# DualBalancedOutput.net
KiCad netlist of a schematic drawn in EAGLE
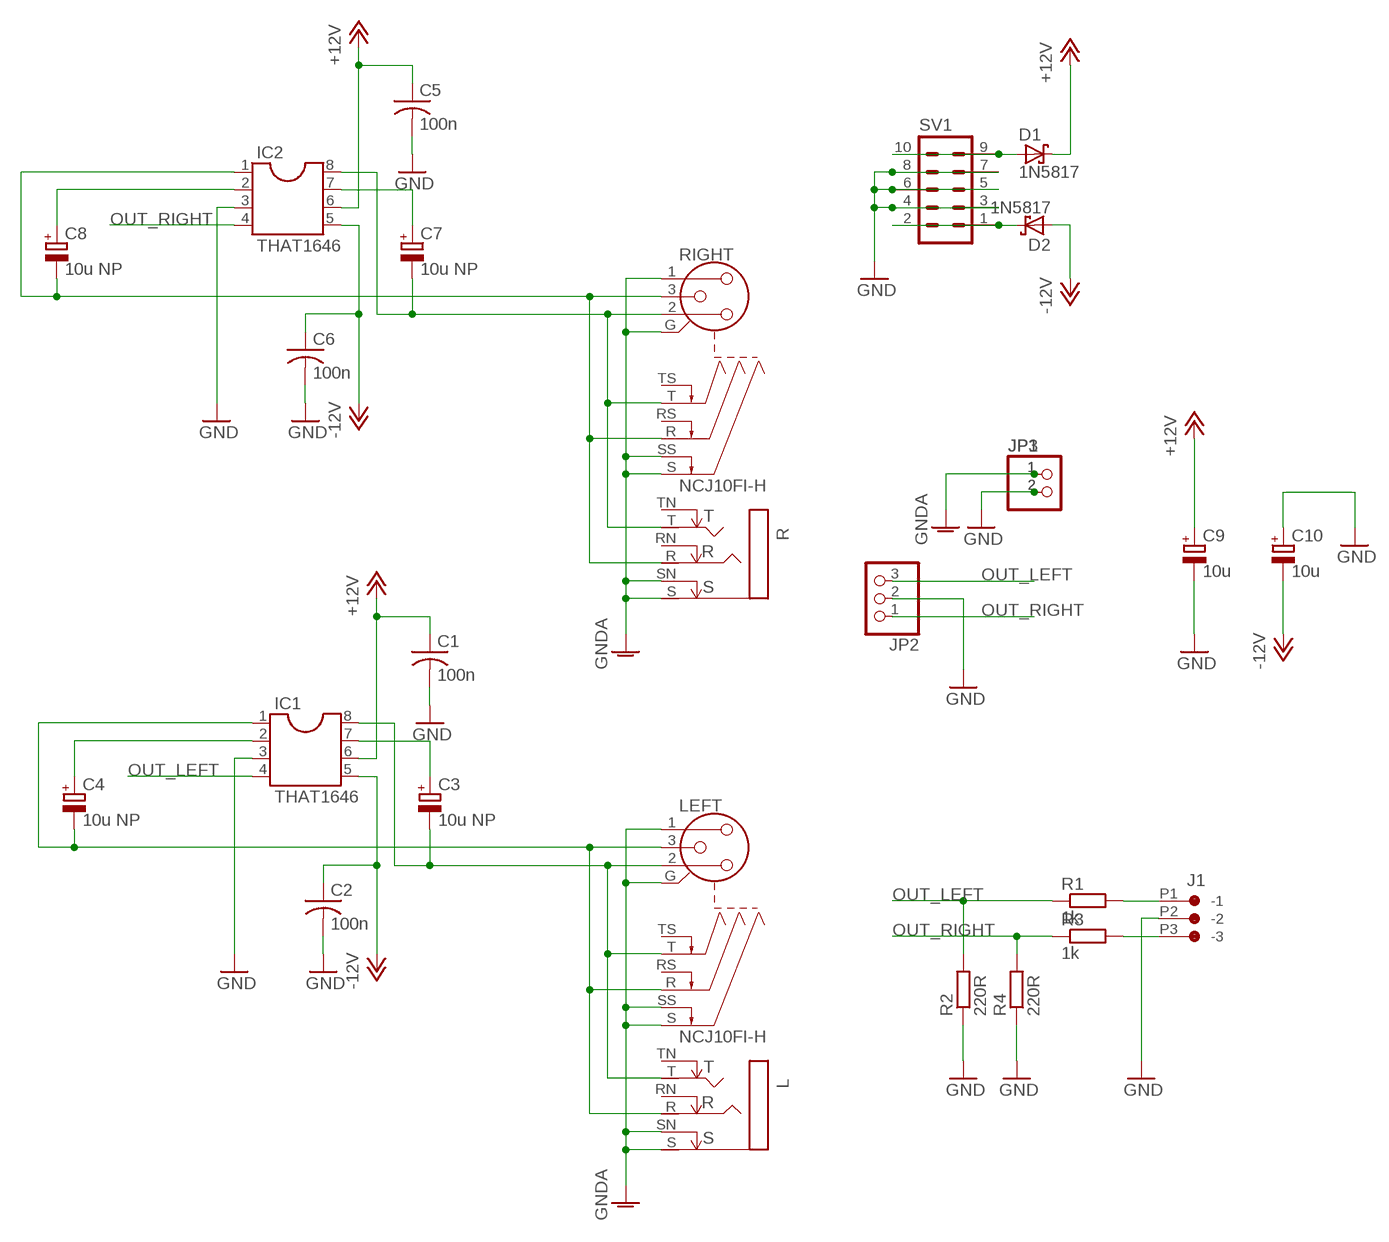
[diagram p0: schematic, sheet 1]

(export (version "E")
  (design (tool "Eeschema 10.0.6"))
  (components
    (comp (ref "C1")
      (value "100n")
      (footprint "eagle-import:C050-024X044")
      (libsource (lib "eagle-import") (part "C-US050-024X044"))
    )
    (comp (ref "C2")
      (value "100n")
      (footprint "eagle-import:C050-024X044")
      (libsource (lib "eagle-import") (part "C-US050-024X044"))
    )
    (comp (ref "C3")
      (value "10u NP")
      (footprint "eagle-import:E2-5")
      (libsource (lib "eagle-import") (part "CPOL-EUE2-5"))
    )
    (comp (ref "C4")
      (value "10u NP")
      (footprint "eagle-import:E2-5")
      (libsource (lib "eagle-import") (part "CPOL-EUE2-5"))
    )
    (comp (ref "C5")
      (value "100n")
      (footprint "eagle-import:C050-024X044")
      (libsource (lib "eagle-import") (part "C-US050-024X044"))
    )
    (comp (ref "C6")
      (value "100n")
      (footprint "eagle-import:C050-024X044")
      (libsource (lib "eagle-import") (part "C-US050-024X044"))
    )
    (comp (ref "C7")
      (value "10u NP")
      (footprint "eagle-import:E2-5")
      (libsource (lib "eagle-import") (part "CPOL-EUE2-5"))
    )
    (comp (ref "C8")
      (value "10u NP")
      (footprint "eagle-import:E2-5")
      (libsource (lib "eagle-import") (part "CPOL-EUE2-5"))
    )
    (comp (ref "C9")
      (value "10u")
      (footprint "eagle-import:E5-6")
      (libsource (lib "eagle-import") (part "rcl_CPOL-EUE5-6"))
    )
    (comp (ref "C10")
      (value "10u")
      (footprint "eagle-import:E5-6")
      (libsource (lib "eagle-import") (part "rcl_CPOL-EUE5-6"))
    )
    (comp (ref "D1")
      (value "1N5817")
      (footprint "eagle-import:DO41-7.6")
      (libsource (lib "eagle-import") (part "1N5819-B"))
    )
    (comp (ref "D2")
      (value "1N5817")
      (footprint "eagle-import:DO41-7.6")
      (libsource (lib "eagle-import") (part "1N5819-B"))
    )
    (comp (ref "IC1")
      (value "THAT1646")
      (footprint "eagle-import:DIL08")
      (libsource (lib "eagle-import") (part "DIL8"))
    )
    (comp (ref "IC2")
      (value "THAT1646")
      (footprint "eagle-import:DIL08")
      (libsource (lib "eagle-import") (part "DIL8"))
    )
    (comp (ref "J1")
      (value "CON-JST_PH_3W")
      (footprint "eagle-import:CON-JST_PH_3W")
      (libsource (lib "eagle-import") (part "CON-JST_PH_3W"))
    )
    (comp (ref "JP1")
      (value "PINHD-1X2")
      (footprint "eagle-import:1X02")
      (libsource (lib "eagle-import") (part "PINHD-1X2"))
    )
    (comp (ref "JP2")
      (value "PINHD-1X3")
      (footprint "eagle-import:1X03")
      (libsource (lib "eagle-import") (part "PINHD-1X3"))
    )
    (comp (ref "JP3")
      (value "PINHD-1X2")
      (footprint "eagle-import:1X02")
      (libsource (lib "eagle-import") (part "PINHD-1X2"))
    )
    (comp (ref "L")
      (value "NEUTRIK_NMJ6HCD2")
      (footprint "eagle-import:NMJ6HCD2")
      (libsource (lib "eagle-import") (part "NEUTRIK_NMJ6HCD2"))
    )
    (comp (ref "LEFT")
      (value "NCJ10FI-H")
      (footprint "eagle-import:NCJ10FI-H")
      (libsource (lib "eagle-import") (part "NCJ10FI-H"))
    )
    (comp (ref "R")
      (value "NEUTRIK_NMJ6HCD2")
      (footprint "eagle-import:NMJ6HCD2")
      (libsource (lib "eagle-import") (part "NEUTRIK_NMJ6HCD2"))
    )
    (comp (ref "R1")
      (value "1k")
      (footprint "eagle-import:0204_7")
      (libsource (lib "eagle-import") (part "R-EU_0204/7"))
    )
    (comp (ref "R2")
      (value "220R")
      (footprint "eagle-import:0204_7")
      (libsource (lib "eagle-import") (part "R-EU_0204/7"))
    )
    (comp (ref "R3")
      (value "1k")
      (footprint "eagle-import:0204_7")
      (libsource (lib "eagle-import") (part "R-EU_0204/7"))
    )
    (comp (ref "R4")
      (value "220R")
      (footprint "eagle-import:0204_7")
      (libsource (lib "eagle-import") (part "R-EU_0204/7"))
    )
    (comp (ref "RIGHT")
      (value "NCJ10FI-H")
      (footprint "eagle-import:NCJ10FI-H")
      (libsource (lib "eagle-import") (part "NCJ10FI-H"))
    )
    (comp (ref "SV1")
      (value "MA05-2")
      (footprint "eagle-import:MA05-2")
      (libsource (lib "eagle-import") (part "MA05-2"))
    )
  )
  (nets
    (net (code "1") (name "+12V") (class "Default")
      (node (ref "C1") (pin "1") (pinfunction "1_1") (pintype "passive"))
      (node (ref "C5") (pin "1") (pinfunction "1_1") (pintype "passive"))
      (node (ref "C9") (pin "+") (pinfunction "+_+") (pintype "passive"))
      (node (ref "D1") (pin "C") (pinfunction "C_C") (pintype "passive"))
      (node (ref "IC1") (pin "6") (pinfunction "6_6") (pintype "passive"))
      (node (ref "IC2") (pin "6") (pinfunction "6_6") (pintype "passive"))
    )
    (net (code "2") (name "-12V") (class "Default")
      (node (ref "C10") (pin "-") (pinfunction "-_-") (pintype "passive"))
      (node (ref "C2") (pin "1") (pinfunction "1_1") (pintype "passive"))
      (node (ref "C6") (pin "1") (pinfunction "1_1") (pintype "passive"))
      (node (ref "D2") (pin "A") (pinfunction "A_A") (pintype "passive"))
      (node (ref "IC1") (pin "5") (pinfunction "5_5") (pintype "passive"))
      (node (ref "IC2") (pin "5") (pinfunction "5_5") (pintype "passive"))
    )
    (net (code "3") (name "/OUT_LEFT") (class "Default")
      (node (ref "IC1") (pin "4") (pinfunction "4_4") (pintype "passive"))
      (node (ref "JP2") (pin "3") (pinfunction "3_3") (pintype "passive"))
      (node (ref "R1") (pin "1") (pinfunction "1_1") (pintype "passive"))
      (node (ref "R2") (pin "2") (pinfunction "2_2") (pintype "passive"))
    )
    (net (code "4") (name "/OUT_RIGHT") (class "Default")
      (node (ref "IC2") (pin "4") (pinfunction "4_4") (pintype "passive"))
      (node (ref "JP2") (pin "1") (pinfunction "1_1") (pintype "passive"))
      (node (ref "R3") (pin "1") (pinfunction "1_1") (pintype "passive"))
      (node (ref "R4") (pin "2") (pinfunction "2_2") (pintype "passive"))
    )
    (net (code "5") (name "GND") (class "Default")
      (node (ref "C1") (pin "2") (pinfunction "2_2") (pintype "passive"))
      (node (ref "C10") (pin "+") (pinfunction "+_+") (pintype "passive"))
      (node (ref "C2") (pin "2") (pinfunction "2_2") (pintype "passive"))
      (node (ref "C5") (pin "2") (pinfunction "2_2") (pintype "passive"))
      (node (ref "C6") (pin "2") (pinfunction "2_2") (pintype "passive"))
      (node (ref "C9") (pin "-") (pinfunction "-_-") (pintype "passive"))
      (node (ref "IC1") (pin "3") (pinfunction "3_3") (pintype "passive"))
      (node (ref "IC2") (pin "3") (pinfunction "3_3") (pintype "passive"))
      (node (ref "J1") (pin "P2") (pinfunction "-2_P2") (pintype "bidirectional"))
      (node (ref "JP1") (pin "2") (pinfunction "2_2") (pintype "passive"))
      (node (ref "JP2") (pin "2") (pinfunction "2_2") (pintype "passive"))
      (node (ref "JP3") (pin "2") (pinfunction "2_2") (pintype "passive"))
      (node (ref "R2") (pin "1") (pinfunction "1_1") (pintype "passive"))
      (node (ref "R4") (pin "1") (pinfunction "1_1") (pintype "passive"))
      (node (ref "SV1") (pin "3") (pinfunction "3_3") (pintype "passive"))
      (node (ref "SV1") (pin "4") (pinfunction "4_4") (pintype "passive"))
      (node (ref "SV1") (pin "5") (pinfunction "5_5") (pintype "passive"))
      (node (ref "SV1") (pin "6") (pinfunction "6_6") (pintype "passive"))
      (node (ref "SV1") (pin "7") (pinfunction "7_7") (pintype "passive"))
      (node (ref "SV1") (pin "8") (pinfunction "8_8") (pintype "passive"))
    )
    (net (code "6") (name "GNDA") (class "Default")
      (node (ref "JP1") (pin "1") (pinfunction "1_1") (pintype "passive"))
      (node (ref "JP3") (pin "1") (pinfunction "1_1") (pintype "passive"))
      (node (ref "L") (pin "S") (pinfunction "S_S") (pintype "passive"))
      (node (ref "L") (pin "SN") (pinfunction "SN_SN") (pintype "passive"))
      (node (ref "LEFT") (pin "1") (pinfunction "1_1") (pintype "passive"))
      (node (ref "LEFT") (pin "G") (pinfunction "G_G") (pintype "passive"))
      (node (ref "LEFT") (pin "S") (pinfunction "S_S") (pintype "passive"))
      (node (ref "LEFT") (pin "SS") (pinfunction "SS_SS") (pintype "passive"))
      (node (ref "R") (pin "S") (pinfunction "S_S") (pintype "passive"))
      (node (ref "R") (pin "SN") (pinfunction "SN_SN") (pintype "passive"))
      (node (ref "RIGHT") (pin "1") (pinfunction "1_1") (pintype "passive"))
      (node (ref "RIGHT") (pin "G") (pinfunction "G_G") (pintype "passive"))
      (node (ref "RIGHT") (pin "S") (pinfunction "S_S") (pintype "passive"))
      (node (ref "RIGHT") (pin "SS") (pinfunction "SS_SS") (pintype "passive"))
    )
    (net (code "7") (name "Net-(C3-Pad+)") (class "Default")
      (node (ref "C3") (pin "+") (pinfunction "+_+") (pintype "passive"))
      (node (ref "IC1") (pin "7") (pinfunction "7_7") (pintype "passive"))
    )
    (net (code "8") (name "Net-(C3-Pad-)") (class "Default")
      (node (ref "C3") (pin "-") (pinfunction "-_-") (pintype "passive"))
      (node (ref "IC1") (pin "8") (pinfunction "8_8") (pintype "passive"))
      (node (ref "L") (pin "T") (pinfunction "T_T") (pintype "passive"))
      (node (ref "LEFT") (pin "2") (pinfunction "2_2") (pintype "passive"))
      (node (ref "LEFT") (pin "T") (pinfunction "T_T") (pintype "passive"))
    )
    (net (code "9") (name "Net-(C4-Pad+)") (class "Default")
      (node (ref "C4") (pin "+") (pinfunction "+_+") (pintype "passive"))
      (node (ref "IC1") (pin "2") (pinfunction "2_2") (pintype "passive"))
    )
    (net (code "10") (name "Net-(C4-Pad-)") (class "Default")
      (node (ref "C4") (pin "-") (pinfunction "-_-") (pintype "passive"))
      (node (ref "IC1") (pin "1") (pinfunction "1_1") (pintype "passive"))
      (node (ref "L") (pin "R") (pinfunction "R_R") (pintype "passive"))
      (node (ref "LEFT") (pin "3") (pinfunction "3_3") (pintype "passive"))
      (node (ref "LEFT") (pin "R") (pinfunction "R_R") (pintype "passive"))
    )
    (net (code "11") (name "Net-(C7-Pad+)") (class "Default")
      (node (ref "C7") (pin "+") (pinfunction "+_+") (pintype "passive"))
      (node (ref "IC2") (pin "7") (pinfunction "7_7") (pintype "passive"))
    )
    (net (code "12") (name "Net-(C7-Pad-)") (class "Default")
      (node (ref "C7") (pin "-") (pinfunction "-_-") (pintype "passive"))
      (node (ref "IC2") (pin "8") (pinfunction "8_8") (pintype "passive"))
      (node (ref "R") (pin "T") (pinfunction "T_T") (pintype "passive"))
      (node (ref "RIGHT") (pin "2") (pinfunction "2_2") (pintype "passive"))
      (node (ref "RIGHT") (pin "T") (pinfunction "T_T") (pintype "passive"))
    )
    (net (code "13") (name "Net-(C8-Pad+)") (class "Default")
      (node (ref "C8") (pin "+") (pinfunction "+_+") (pintype "passive"))
      (node (ref "IC2") (pin "2") (pinfunction "2_2") (pintype "passive"))
    )
    (net (code "14") (name "Net-(C8-Pad-)") (class "Default")
      (node (ref "C8") (pin "-") (pinfunction "-_-") (pintype "passive"))
      (node (ref "IC2") (pin "1") (pinfunction "1_1") (pintype "passive"))
      (node (ref "R") (pin "R") (pinfunction "R_R") (pintype "passive"))
      (node (ref "RIGHT") (pin "3") (pinfunction "3_3") (pintype "passive"))
      (node (ref "RIGHT") (pin "R") (pinfunction "R_R") (pintype "passive"))
    )
    (net (code "15") (name "Net-(D1-PadA)") (class "Default")
      (node (ref "D1") (pin "A") (pinfunction "A_A") (pintype "passive"))
      (node (ref "SV1") (pin "10") (pinfunction "10_10") (pintype "passive"))
      (node (ref "SV1") (pin "9") (pinfunction "9_9") (pintype "passive"))
    )
    (net (code "16") (name "Net-(D2-PadC)") (class "Default")
      (node (ref "D2") (pin "C") (pinfunction "C_C") (pintype "passive"))
      (node (ref "SV1") (pin "1") (pinfunction "1_1") (pintype "passive"))
      (node (ref "SV1") (pin "2") (pinfunction "2_2") (pintype "passive"))
    )
    (net (code "17") (name "Net-(J1--1)") (class "Default")
      (node (ref "J1") (pin "P1") (pinfunction "-1_P1") (pintype "bidirectional"))
      (node (ref "R1") (pin "2") (pinfunction "2_2") (pintype "passive"))
    )
    (net (code "18") (name "Net-(J1--3)") (class "Default")
      (node (ref "J1") (pin "P3") (pinfunction "-3_P3") (pintype "bidirectional"))
      (node (ref "R3") (pin "2") (pinfunction "2_2") (pintype "passive"))
    )
    (net (code "19") (name "unconnected-(L-PadRN)") (class "Default")
      (node (ref "L") (pin "RN") (pinfunction "RN_RN") (pintype "passive"))
    )
    (net (code "20") (name "unconnected-(L-PadTN)") (class "Default")
      (node (ref "L") (pin "TN") (pinfunction "TN_TN") (pintype "passive"))
    )
    (net (code "21") (name "unconnected-(LEFT-PadRS)") (class "Default")
      (node (ref "LEFT") (pin "RS") (pinfunction "RS_RS") (pintype "passive"))
    )
    (net (code "22") (name "unconnected-(LEFT-PadTS)") (class "Default")
      (node (ref "LEFT") (pin "TS") (pinfunction "TS_TS") (pintype "passive"))
    )
    (net (code "23") (name "unconnected-(R-PadRN)") (class "Default")
      (node (ref "R") (pin "RN") (pinfunction "RN_RN") (pintype "passive"))
    )
    (net (code "24") (name "unconnected-(R-PadTN)") (class "Default")
      (node (ref "R") (pin "TN") (pinfunction "TN_TN") (pintype "passive"))
    )
    (net (code "25") (name "unconnected-(RIGHT-PadRS)") (class "Default")
      (node (ref "RIGHT") (pin "RS") (pinfunction "RS_RS") (pintype "passive"))
    )
    (net (code "26") (name "unconnected-(RIGHT-PadTS)") (class "Default")
      (node (ref "RIGHT") (pin "TS") (pinfunction "TS_TS") (pintype "passive"))
    )
  )
)
